# STM32L441CE_2L.net
KiCad netlist of a schematic drawn in EAGLE
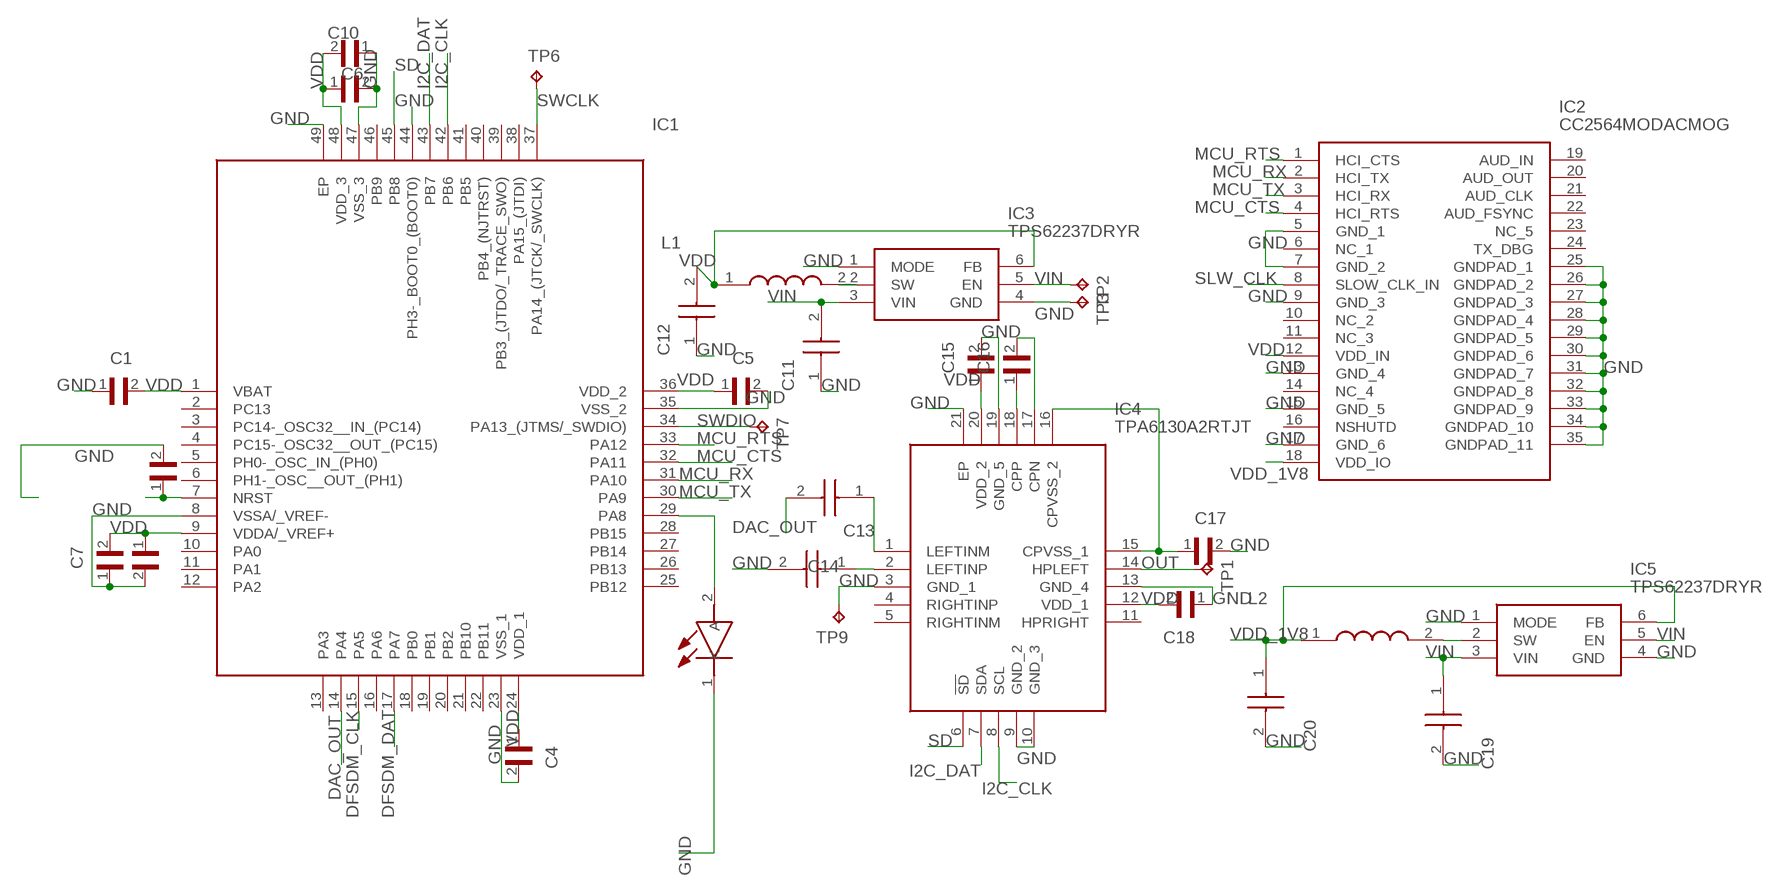
[diagram p0: schematic, sheet 1]
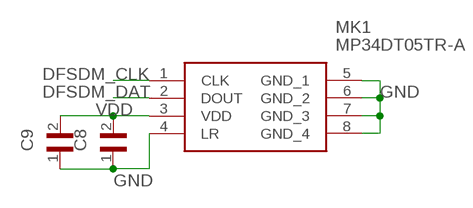
[diagram p1: schematic, sheet 2]

(export (version "E")
  (design (tool "Eeschema 10.0.6"))
  (components
    (comp (ref "C1")
      (value "GRM033C80J104KE15D")
      (footprint "eagle-import:CAPC0603X33N")
      (fields (field (name "DIGI-KEY_PART_NUMBER") "490-10390-1-ND") (field (name "MF") "Murata Electronics"))
      (libsource (lib "eagle-import") (part "GRM033C80J104KE15D"))
    )
    (comp (ref "C2")
      (value "GRM033C80J104KE15D")
      (footprint "eagle-import:CAPC0603X33N")
      (fields (field (name "DIGI-KEY_PART_NUMBER") "490-10390-1-ND") (field (name "MF") "Murata Electronics"))
      (libsource (lib "eagle-import") (part "GRM033C80J104KE15D"))
    )
    (comp (ref "C3")
      (value "GRM033C80J104KE15D")
      (footprint "eagle-import:CAPC0603X33N")
      (fields (field (name "DIGI-KEY_PART_NUMBER") "490-10390-1-ND") (field (name "MF") "Murata Electronics"))
      (libsource (lib "eagle-import") (part "GRM033C80J104KE15D"))
    )
    (comp (ref "C4")
      (value "GRM033C80J104KE15D")
      (footprint "eagle-import:CAPC0603X33N")
      (fields (field (name "DIGI-KEY_PART_NUMBER") "490-10390-1-ND") (field (name "MF") "Murata Electronics"))
      (libsource (lib "eagle-import") (part "GRM033C80J104KE15D"))
    )
    (comp (ref "C5")
      (value "GRM033C80J104KE15D")
      (footprint "eagle-import:CAPC0603X33N")
      (fields (field (name "DIGI-KEY_PART_NUMBER") "490-10390-1-ND") (field (name "MF") "Murata Electronics"))
      (libsource (lib "eagle-import") (part "GRM033C80J104KE15D"))
    )
    (comp (ref "C6")
      (value "GRM033C80J104KE15D")
      (footprint "eagle-import:CAPC0603X33N")
      (fields (field (name "DIGI-KEY_PART_NUMBER") "490-10390-1-ND") (field (name "MF") "Murata Electronics"))
      (libsource (lib "eagle-import") (part "GRM033C80J104KE15D"))
    )
    (comp (ref "C7")
      (value "JMK105C6105KV-F")
      (footprint "eagle-import:CAPC1005X55N")
      (fields (field (name "DIGI-KEY_PART_NUMBER") "587-3381-1-ND") (field (name "MF") "Taiyo Yuden"))
      (libsource (lib "eagle-import") (part "JMK105C6105KV-F"))
    )
    (comp (ref "C10")
      (value "GRM155R60J475ME47D")
      (footprint "eagle-import:CAPC1005X60N")
      (fields (field (name "DIGI-KEY_PART_NUMBER") "490-5915-1-ND") (field (name "MF") "Murata"))
      (libsource (lib "eagle-import") (part "GRM155R60J475ME47D"))
    )
    (comp (ref "C11")
      (value "02016D225MAT2A")
      (footprint "eagle-import:CAPC0603X33N")
      (fields (field (name "MOUSER_PART_NUMBER") "581-02016D225MAT2A"))
      (libsource (lib "eagle-import") (part "02016D225MAT2A"))
    )
    (comp (ref "C12")
      (value "GRM035R60J475ME15D")
      (footprint "eagle-import:CAPC0603X55N")
      (fields (field (name "MOUSER_PART_NUMBER") "81-GRM035R60J475ME5D"))
      (libsource (lib "eagle-import") (part "GRM035R60J475ME15D"))
    )
    (comp (ref "C13")
      (value "CL03A474KQ3NNNC")
      (footprint "eagle-import:CAPC0603X33N")
      (libsource (lib "eagle-import") (part "CL03A474KQ3NNNC"))
    )
    (comp (ref "C14")
      (value "CL03A474KQ3NNNC")
      (footprint "eagle-import:CAPC0603X33N")
      (libsource (lib "eagle-import") (part "CL03A474KQ3NNNC"))
    )
    (comp (ref "C15")
      (value "JMK105C6105KV-F")
      (footprint "eagle-import:CAPC1005X55N")
      (fields (field (name "DIGI-KEY_PART_NUMBER") "587-3381-1-ND") (field (name "MF") "Taiyo Yuden"))
      (libsource (lib "eagle-import") (part "JMK105C6105KV-F"))
    )
    (comp (ref "C16")
      (value "JMK105C6105KV-F")
      (footprint "eagle-import:CAPC1005X55N")
      (fields (field (name "DIGI-KEY_PART_NUMBER") "587-3381-1-ND") (field (name "MF") "Taiyo Yuden"))
      (libsource (lib "eagle-import") (part "JMK105C6105KV-F"))
    )
    (comp (ref "C17")
      (value "JMK105C6105KV-F")
      (footprint "eagle-import:CAPC1005X55N")
      (fields (field (name "DIGI-KEY_PART_NUMBER") "587-3381-1-ND") (field (name "MF") "Taiyo Yuden"))
      (libsource (lib "eagle-import") (part "JMK105C6105KV-F"))
    )
    (comp (ref "C18")
      (value "JMK105C6105KV-F")
      (footprint "eagle-import:CAPC1005X55N")
      (fields (field (name "DIGI-KEY_PART_NUMBER") "587-3381-1-ND") (field (name "MF") "Taiyo Yuden"))
      (libsource (lib "eagle-import") (part "JMK105C6105KV-F"))
    )
    (comp (ref "C19")
      (value "02016D225MAT2A")
      (footprint "eagle-import:CAPC0603X33N")
      (fields (field (name "MOUSER_PART_NUMBER") "581-02016D225MAT2A"))
      (libsource (lib "eagle-import") (part "02016D225MAT2A"))
    )
    (comp (ref "C20")
      (value "GRM035R60J475ME15D")
      (footprint "eagle-import:CAPC0603X55N")
      (fields (field (name "MOUSER_PART_NUMBER") "81-GRM035R60J475ME5D"))
      (libsource (lib "eagle-import") (part "GRM035R60J475ME15D"))
    )
    (comp (ref "IC1")
      (value "STM32L451CEU6")
      (footprint "eagle-import:QFN50P700X700X60-49N")
      (fields (field (name "MOUSER_PART_NUMBER") "511-STM32L451CEU6"))
      (libsource (lib "eagle-import") (part "STM32L451CEU6"))
    )
    (comp (ref "IC2")
      (value "CC2564MODACMOG")
      (footprint "eagle-import:MOG0035A")
      (fields (field (name "MOUSER_PART_NUMBER") "595-CC2564MODACMOG"))
      (libsource (lib "eagle-import") (part "CC2564MODACMOG"))
    )
    (comp (ref "IC3")
      (value "TPS62237DRYR")
      (footprint "eagle-import:SON50P100X145X60-6N")
      (fields (field (name "MOUSER_PART_NUMBER") "595-TPS62237DRYR"))
      (libsource (lib "eagle-import") (part "TPS62237DRYR"))
    )
    (comp (ref "IC4")
      (value "TPA6130A2RTJT")
      (footprint "eagle-import:QFN50P400X400X80-21N")
      (fields (field (name "MOUSER_PART_NUMBER") "595-TPA6130A2RTJT"))
      (libsource (lib "eagle-import") (part "TPA6130A2RTJT"))
    )
    (comp (ref "IC5")
      (value "TPS62237DRYR")
      (footprint "eagle-import:SON50P100X145X60-6N")
      (fields (field (name "MOUSER_PART_NUMBER") "595-TPS62237DRYR"))
      (libsource (lib "eagle-import") (part "TPS62237DRYR"))
    )
    (comp (ref "L1")
      (value "MLZ1005M2R2WT000")
      (footprint "eagle-import:INDC1005X55N")
      (fields (field (name "MOUSER_PART_NUMBER") "810-MLZ1005M2R2WT000"))
      (libsource (lib "eagle-import") (part "MLZ1005M2R2WT000"))
    )
    (comp (ref "L2")
      (value "MLZ1005M2R2WT000")
      (footprint "eagle-import:INDC1005X55N")
      (fields (field (name "MOUSER_PART_NUMBER") "810-MLZ1005M2R2WT000"))
      (libsource (lib "eagle-import") (part "MLZ1005M2R2WT000"))
    )
    (comp (ref "LED1")
      (value "VLMS1500-GS08")
      (footprint "eagle-import:VLMG1500GS08")
      (fields (field (name "MOUSER_PART_NUMBER") "78-VLMS1500-GS08"))
      (libsource (lib "eagle-import") (part "VLMS1500-GS08"))
    )
    (comp (ref "TP1")
      (value "TPTP11R")
      (footprint "eagle-import:TP11R")
      (libsource (lib "eagle-import") (part "TPTP11R"))
    )
    (comp (ref "TP2")
      (value "TPTP11R")
      (footprint "eagle-import:TP11R")
      (libsource (lib "eagle-import") (part "TPTP11R"))
    )
    (comp (ref "TP3")
      (value "TPTP11R")
      (footprint "eagle-import:TP11R")
      (libsource (lib "eagle-import") (part "TPTP11R"))
    )
    (comp (ref "TP6")
      (value "TPTP11R")
      (footprint "eagle-import:TP11R")
      (libsource (lib "eagle-import") (part "TPTP11R"))
    )
    (comp (ref "TP7")
      (value "TPTP11R")
      (footprint "eagle-import:TP11R")
      (libsource (lib "eagle-import") (part "TPTP11R"))
    )
    (comp (ref "TP9")
      (value "TPTP11R")
      (footprint "eagle-import:TP11R")
      (libsource (lib "eagle-import") (part "TPTP11R"))
    )
    (comp (ref "C8")
      (value "JMK105C6105KV-F")
      (footprint "eagle-import:CAPC1005X55N")
      (fields (field (name "DIGI-KEY_PART_NUMBER") "587-3381-1-ND") (field (name "MF") "Taiyo Yuden"))
      (libsource (lib "eagle-import") (part "JMK105C6105KV-F"))
    )
    (comp (ref "C9")
      (value "GRM033C80J104KE15D")
      (footprint "eagle-import:CAPC0603X33N")
      (fields (field (name "DIGI-KEY_PART_NUMBER") "490-10390-1-ND") (field (name "MF") "Murata Electronics"))
      (libsource (lib "eagle-import") (part "GRM033C80J104KE15D"))
    )
    (comp (ref "MK1")
      (value "MP34DT05TR-A")
      (footprint "eagle-import:MP34DT05TRA")
      (fields (field (name "MOUSER_PART_NUMBER") "511-MP34DT05TR-A"))
      (libsource (lib "eagle-import") (part "MP34DT05TR-A"))
    )
  )
  (nets
    (net (code "1") (name "DAC_OUT") (class "Default")
      (node (ref "C13") (pin "2") (pinfunction "2_2") (pintype "bidirectional"))
      (node (ref "IC1") (pin "14") (pinfunction "PA4_14") (pintype "bidirectional"))
    )
    (net (code "2") (name "DFSDM_CLK") (class "Default")
      (node (ref "IC1") (pin "15") (pinfunction "PA5_15") (pintype "bidirectional"))
      (node (ref "MK1") (pin "1") (pinfunction "CLK_1") (pintype "bidirectional"))
    )
    (net (code "3") (name "DFSDM_DAT") (class "Default")
      (node (ref "IC1") (pin "17") (pinfunction "PA7_17") (pintype "bidirectional"))
      (node (ref "MK1") (pin "2") (pinfunction "DOUT_2") (pintype "bidirectional"))
    )
    (net (code "4") (name "GND") (class "Default")
      (node (ref "C1") (pin "1") (pinfunction "1_1") (pintype "passive"))
      (node (ref "C10") (pin "1") (pinfunction "1_1") (pintype "passive"))
      (node (ref "C11") (pin "1") (pinfunction "1_1") (pintype "bidirectional"))
      (node (ref "C12") (pin "1") (pinfunction "1_1") (pintype "bidirectional"))
      (node (ref "C14") (pin "2") (pinfunction "2_2") (pintype "bidirectional"))
      (node (ref "C15") (pin "2") (pinfunction "2_2") (pintype "passive"))
      (node (ref "C17") (pin "2") (pinfunction "2_2") (pintype "passive"))
      (node (ref "C18") (pin "1") (pinfunction "1_1") (pintype "passive"))
      (node (ref "C19") (pin "2") (pinfunction "2_2") (pintype "bidirectional"))
      (node (ref "C2") (pin "2") (pinfunction "2_2") (pintype "passive"))
      (node (ref "C20") (pin "2") (pinfunction "2_2") (pintype "bidirectional"))
      (node (ref "C3") (pin "2") (pinfunction "2_2") (pintype "passive"))
      (node (ref "C4") (pin "2") (pinfunction "2_2") (pintype "passive"))
      (node (ref "C5") (pin "2") (pinfunction "2_2") (pintype "passive"))
      (node (ref "C6") (pin "2") (pinfunction "2_2") (pintype "passive"))
      (node (ref "C7") (pin "1") (pinfunction "1_1") (pintype "passive"))
      (node (ref "C8") (pin "1") (pinfunction "1_1") (pintype "passive"))
      (node (ref "C9") (pin "1") (pinfunction "1_1") (pintype "passive"))
      (node (ref "IC1") (pin "23") (pinfunction "VSS_1_23") (pintype "bidirectional"))
      (node (ref "IC1") (pin "35") (pinfunction "VSS_2_35") (pintype "bidirectional"))
      (node (ref "IC1") (pin "44") (pinfunction "PH3-_BOOT0_(BOOT0)_44") (pintype "bidirectional"))
      (node (ref "IC1") (pin "47") (pinfunction "VSS_3_47") (pintype "bidirectional"))
      (node (ref "IC1") (pin "49") (pinfunction "EP_49") (pintype "bidirectional"))
      (node (ref "IC1") (pin "8") (pinfunction "VSSA/_VREF-_8") (pintype "bidirectional"))
      (node (ref "IC2") (pin "13") (pinfunction "GND_4_13") (pintype "power_in"))
      (node (ref "IC2") (pin "15") (pinfunction "GND_5_15") (pintype "power_in"))
      (node (ref "IC2") (pin "17") (pinfunction "GND_6_17") (pintype "power_in"))
      (node (ref "IC2") (pin "25") (pinfunction "GNDPAD_1_25") (pintype "power_in"))
      (node (ref "IC2") (pin "26") (pinfunction "GNDPAD_2_26") (pintype "power_in"))
      (node (ref "IC2") (pin "27") (pinfunction "GNDPAD_3_27") (pintype "power_in"))
      (node (ref "IC2") (pin "28") (pinfunction "GNDPAD_4_28") (pintype "power_in"))
      (node (ref "IC2") (pin "29") (pinfunction "GNDPAD_5_29") (pintype "power_in"))
      (node (ref "IC2") (pin "30") (pinfunction "GNDPAD_6_30") (pintype "power_in"))
      (node (ref "IC2") (pin "31") (pinfunction "GNDPAD_7_31") (pintype "power_in"))
      (node (ref "IC2") (pin "32") (pinfunction "GNDPAD_8_32") (pintype "power_in"))
      (node (ref "IC2") (pin "33") (pinfunction "GNDPAD_9_33") (pintype "power_in"))
      (node (ref "IC2") (pin "34") (pinfunction "GNDPAD_10_34") (pintype "power_in"))
      (node (ref "IC2") (pin "35") (pinfunction "GNDPAD_11_35") (pintype "power_in"))
      (node (ref "IC2") (pin "5") (pinfunction "GND_1_5") (pintype "power_in"))
      (node (ref "IC2") (pin "7") (pinfunction "GND_2_7") (pintype "power_in"))
      (node (ref "IC2") (pin "9") (pinfunction "GND_3_9") (pintype "power_in"))
      (node (ref "IC3") (pin "1") (pinfunction "MODE_1") (pintype "bidirectional"))
      (node (ref "IC3") (pin "4") (pinfunction "GND_4") (pintype "bidirectional"))
      (node (ref "IC4") (pin "10") (pinfunction "GND_3_10") (pintype "bidirectional"))
      (node (ref "IC4") (pin "13") (pinfunction "GND_4_13") (pintype "bidirectional"))
      (node (ref "IC4") (pin "19") (pinfunction "GND_5_19") (pintype "bidirectional"))
      (node (ref "IC4") (pin "21") (pinfunction "EP_21") (pintype "bidirectional"))
      (node (ref "IC4") (pin "3") (pinfunction "GND_1_3") (pintype "bidirectional"))
      (node (ref "IC4") (pin "9") (pinfunction "GND_2_9") (pintype "bidirectional"))
      (node (ref "IC5") (pin "1") (pinfunction "MODE_1") (pintype "bidirectional"))
      (node (ref "IC5") (pin "4") (pinfunction "GND_4") (pintype "bidirectional"))
      (node (ref "LED1") (pin "1") (pinfunction "K_1") (pintype "bidirectional"))
      (node (ref "MK1") (pin "4") (pinfunction "LR_4") (pintype "bidirectional"))
      (node (ref "MK1") (pin "5") (pinfunction "GND_1_5") (pintype "bidirectional"))
      (node (ref "MK1") (pin "6") (pinfunction "GND_2_6") (pintype "bidirectional"))
      (node (ref "MK1") (pin "7") (pinfunction "GND_3_7") (pintype "bidirectional"))
      (node (ref "MK1") (pin "8") (pinfunction "GND_4_8") (pintype "bidirectional"))
      (node (ref "TP3") (pin "TP") (pinfunction "TP_TP") (pintype "input"))
      (node (ref "TP9") (pin "TP") (pinfunction "TP_TP") (pintype "input"))
    )
    (net (code "5") (name "I2C_CLK") (class "Default")
      (node (ref "IC1") (pin "42") (pinfunction "PB6_42") (pintype "bidirectional"))
      (node (ref "IC4") (pin "8") (pinfunction "SCL_8") (pintype "bidirectional"))
    )
    (net (code "6") (name "I2C_DAT") (class "Default")
      (node (ref "IC1") (pin "43") (pinfunction "PB7_43") (pintype "bidirectional"))
      (node (ref "IC4") (pin "7") (pinfunction "SDA_7") (pintype "bidirectional"))
    )
    (net (code "7") (name "MCU_CTS") (class "Default")
      (node (ref "IC1") (pin "32") (pinfunction "PA11_32") (pintype "bidirectional"))
      (node (ref "IC2") (pin "4") (pinfunction "HCI_RTS_4") (pintype "output"))
    )
    (net (code "8") (name "MCU_RTS") (class "Default")
      (node (ref "IC1") (pin "33") (pinfunction "PA12_33") (pintype "bidirectional"))
      (node (ref "IC2") (pin "1") (pinfunction "HCI_CTS_1") (pintype "input"))
    )
    (net (code "9") (name "MCU_RX") (class "Default")
      (node (ref "IC1") (pin "31") (pinfunction "PA10_31") (pintype "bidirectional"))
      (node (ref "IC2") (pin "2") (pinfunction "HCI_TX_2") (pintype "output"))
    )
    (net (code "10") (name "MCU_TX") (class "Default")
      (node (ref "IC1") (pin "30") (pinfunction "PA9_30") (pintype "bidirectional"))
      (node (ref "IC2") (pin "3") (pinfunction "HCI_RX_3") (pintype "input"))
    )
    (net (code "11") (name "Net-(IC1-NRST)") (class "Default")
      (node (ref "C2") (pin "1") (pinfunction "1_1") (pintype "passive"))
      (node (ref "IC1") (pin "7") (pinfunction "NRST_7") (pintype "bidirectional"))
    )
    (net (code "12") (name "Net-(IC1-PA8)") (class "Default")
      (node (ref "IC1") (pin "29") (pinfunction "PA8_29") (pintype "bidirectional"))
      (node (ref "LED1") (pin "2") (pinfunction "A_2") (pintype "bidirectional"))
    )
    (net (code "13") (name "Net-(IC3-SW)") (class "Default")
      (node (ref "IC3") (pin "2") (pinfunction "SW_2") (pintype "bidirectional"))
      (node (ref "L1") (pin "2") (pinfunction "2_2") (pintype "bidirectional"))
    )
    (net (code "14") (name "Net-(IC4-CPN)") (class "Default")
      (node (ref "C16") (pin "2") (pinfunction "2_2") (pintype "passive"))
      (node (ref "IC4") (pin "17") (pinfunction "CPN_17") (pintype "bidirectional"))
    )
    (net (code "15") (name "Net-(IC4-CPP)") (class "Default")
      (node (ref "C16") (pin "1") (pinfunction "1_1") (pintype "passive"))
      (node (ref "IC4") (pin "18") (pinfunction "CPP_18") (pintype "bidirectional"))
    )
    (net (code "16") (name "Net-(IC4-CPVSS_1)") (class "Default")
      (node (ref "C17") (pin "1") (pinfunction "1_1") (pintype "passive"))
      (node (ref "IC4") (pin "15") (pinfunction "CPVSS_1_15") (pintype "bidirectional"))
      (node (ref "IC4") (pin "16") (pinfunction "CPVSS_2_16") (pintype "bidirectional"))
    )
    (net (code "17") (name "Net-(IC4-LEFTINM)") (class "Default")
      (node (ref "C13") (pin "1") (pinfunction "1_1") (pintype "bidirectional"))
      (node (ref "IC4") (pin "1") (pinfunction "LEFTINM_1") (pintype "bidirectional"))
    )
    (net (code "18") (name "Net-(IC4-LEFTINP)") (class "Default")
      (node (ref "C14") (pin "1") (pinfunction "1_1") (pintype "bidirectional"))
      (node (ref "IC4") (pin "2") (pinfunction "LEFTINP_2") (pintype "bidirectional"))
    )
    (net (code "19") (name "Net-(IC5-SW)") (class "Default")
      (node (ref "IC5") (pin "2") (pinfunction "SW_2") (pintype "bidirectional"))
      (node (ref "L2") (pin "2") (pinfunction "2_2") (pintype "bidirectional"))
    )
    (net (code "20") (name "OUT") (class "Default")
      (node (ref "IC4") (pin "14") (pinfunction "HPLEFT_14") (pintype "bidirectional"))
      (node (ref "TP1") (pin "TP") (pinfunction "TP_TP") (pintype "input"))
    )
    (net (code "21") (name "SD") (class "Default")
      (node (ref "IC1") (pin "45") (pinfunction "PB8_45") (pintype "bidirectional"))
      (node (ref "IC4") (pin "6") (pinfunction "~{SD}_6") (pintype "bidirectional"))
    )
    (net (code "22") (name "SLW_CLK") (class "Default")
      (node (ref "IC2") (pin "8") (pinfunction "SLOW_CLK_IN_8") (pintype "input"))
    )
    (net (code "23") (name "SWCLK") (class "Default")
      (node (ref "IC1") (pin "37") (pinfunction "PA14_(JTCK/_SWCLK)_37") (pintype "bidirectional"))
      (node (ref "TP6") (pin "TP") (pinfunction "TP_TP") (pintype "input"))
    )
    (net (code "24") (name "SWDIO") (class "Default")
      (node (ref "IC1") (pin "34") (pinfunction "PA13_(JTMS/_SWDIO)_34") (pintype "bidirectional"))
      (node (ref "TP7") (pin "TP") (pinfunction "TP_TP") (pintype "input"))
    )
    (net (code "25") (name "VDD") (class "Default")
      (node (ref "C1") (pin "2") (pinfunction "2_2") (pintype "passive"))
      (node (ref "C10") (pin "2") (pinfunction "2_2") (pintype "passive"))
      (node (ref "C12") (pin "2") (pinfunction "2_2") (pintype "bidirectional"))
      (node (ref "C15") (pin "1") (pinfunction "1_1") (pintype "passive"))
      (node (ref "C18") (pin "2") (pinfunction "2_2") (pintype "passive"))
      (node (ref "C3") (pin "1") (pinfunction "1_1") (pintype "passive"))
      (node (ref "C4") (pin "1") (pinfunction "1_1") (pintype "passive"))
      (node (ref "C5") (pin "1") (pinfunction "1_1") (pintype "passive"))
      (node (ref "C6") (pin "1") (pinfunction "1_1") (pintype "passive"))
      (node (ref "C7") (pin "2") (pinfunction "2_2") (pintype "passive"))
      (node (ref "C8") (pin "2") (pinfunction "2_2") (pintype "passive"))
      (node (ref "C9") (pin "2") (pinfunction "2_2") (pintype "passive"))
      (node (ref "IC1") (pin "1") (pinfunction "VBAT_1") (pintype "bidirectional"))
      (node (ref "IC1") (pin "24") (pinfunction "VDD_1_24") (pintype "bidirectional"))
      (node (ref "IC1") (pin "36") (pinfunction "VDD_2_36") (pintype "bidirectional"))
      (node (ref "IC1") (pin "48") (pinfunction "VDD_3_48") (pintype "bidirectional"))
      (node (ref "IC1") (pin "9") (pinfunction "VDDA/_VREF+_9") (pintype "bidirectional"))
      (node (ref "IC2") (pin "12") (pinfunction "VDD_IN_12") (pintype "input"))
      (node (ref "IC3") (pin "6") (pinfunction "FB_6") (pintype "bidirectional"))
      (node (ref "IC4") (pin "12") (pinfunction "VDD_1_12") (pintype "bidirectional"))
      (node (ref "IC4") (pin "20") (pinfunction "VDD_2_20") (pintype "bidirectional"))
      (node (ref "L1") (pin "1") (pinfunction "1_1") (pintype "bidirectional"))
      (node (ref "MK1") (pin "3") (pinfunction "VDD_3") (pintype "bidirectional"))
    )
    (net (code "26") (name "VDD_1V8") (class "Default")
      (node (ref "C20") (pin "1") (pinfunction "1_1") (pintype "bidirectional"))
      (node (ref "IC2") (pin "18") (pinfunction "VDD_IO_18") (pintype "bidirectional"))
      (node (ref "IC5") (pin "6") (pinfunction "FB_6") (pintype "bidirectional"))
      (node (ref "L2") (pin "1") (pinfunction "1_1") (pintype "bidirectional"))
    )
    (net (code "27") (name "VIN") (class "Default")
      (node (ref "C11") (pin "2") (pinfunction "2_2") (pintype "bidirectional"))
      (node (ref "C19") (pin "1") (pinfunction "1_1") (pintype "bidirectional"))
      (node (ref "IC3") (pin "3") (pinfunction "VIN_3") (pintype "bidirectional"))
      (node (ref "IC3") (pin "5") (pinfunction "EN_5") (pintype "bidirectional"))
      (node (ref "IC5") (pin "3") (pinfunction "VIN_3") (pintype "bidirectional"))
      (node (ref "IC5") (pin "5") (pinfunction "EN_5") (pintype "bidirectional"))
      (node (ref "TP2") (pin "TP") (pinfunction "TP_TP") (pintype "input"))
    )
    (net (code "28") (name "unconnected-(IC1-PA0-Pad10)") (class "Default")
      (node (ref "IC1") (pin "10") (pinfunction "PA0_10") (pintype "bidirectional"))
    )
    (net (code "29") (name "unconnected-(IC1-PA1-Pad11)") (class "Default")
      (node (ref "IC1") (pin "11") (pinfunction "PA1_11") (pintype "bidirectional"))
    )
    (net (code "30") (name "unconnected-(IC1-PA2-Pad12)") (class "Default")
      (node (ref "IC1") (pin "12") (pinfunction "PA2_12") (pintype "bidirectional"))
    )
    (net (code "31") (name "unconnected-(IC1-PA3-Pad13)") (class "Default")
      (node (ref "IC1") (pin "13") (pinfunction "PA3_13") (pintype "bidirectional"))
    )
    (net (code "32") (name "unconnected-(IC1-PA6-Pad16)") (class "Default")
      (node (ref "IC1") (pin "16") (pinfunction "PA6_16") (pintype "bidirectional"))
    )
    (net (code "33") (name "unconnected-(IC1-PA15_(JTDI)-Pad38)") (class "Default")
      (node (ref "IC1") (pin "38") (pinfunction "PA15_(JTDI)_38") (pintype "bidirectional"))
    )
    (net (code "34") (name "unconnected-(IC1-PB0-Pad18)") (class "Default")
      (node (ref "IC1") (pin "18") (pinfunction "PB0_18") (pintype "bidirectional"))
    )
    (net (code "35") (name "unconnected-(IC1-PB1-Pad19)") (class "Default")
      (node (ref "IC1") (pin "19") (pinfunction "PB1_19") (pintype "bidirectional"))
    )
    (net (code "36") (name "unconnected-(IC1-PB2-Pad20)") (class "Default")
      (node (ref "IC1") (pin "20") (pinfunction "PB2_20") (pintype "bidirectional"))
    )
    (net (code "37") (name "unconnected-(IC1-PB3_(JTDO{slash}_TRACE_SWO)-Pad39)") (class "Default")
      (node (ref "IC1") (pin "39") (pinfunction "PB3_(JTDO/_TRACE_SWO)_39") (pintype "bidirectional"))
    )
    (net (code "38") (name "unconnected-(IC1-PB4_(NJTRST)-Pad40)") (class "Default")
      (node (ref "IC1") (pin "40") (pinfunction "PB4_(NJTRST)_40") (pintype "bidirectional"))
    )
    (net (code "39") (name "unconnected-(IC1-PB5-Pad41)") (class "Default")
      (node (ref "IC1") (pin "41") (pinfunction "PB5_41") (pintype "bidirectional"))
    )
    (net (code "40") (name "unconnected-(IC1-PB9-Pad46)") (class "Default")
      (node (ref "IC1") (pin "46") (pinfunction "PB9_46") (pintype "bidirectional"))
    )
    (net (code "41") (name "unconnected-(IC1-PB10-Pad21)") (class "Default")
      (node (ref "IC1") (pin "21") (pinfunction "PB10_21") (pintype "bidirectional"))
    )
    (net (code "42") (name "unconnected-(IC1-PB11-Pad22)") (class "Default")
      (node (ref "IC1") (pin "22") (pinfunction "PB11_22") (pintype "bidirectional"))
    )
    (net (code "43") (name "unconnected-(IC1-PB12-Pad25)") (class "Default")
      (node (ref "IC1") (pin "25") (pinfunction "PB12_25") (pintype "bidirectional"))
    )
    (net (code "44") (name "unconnected-(IC1-PB13-Pad26)") (class "Default")
      (node (ref "IC1") (pin "26") (pinfunction "PB13_26") (pintype "bidirectional"))
    )
    (net (code "45") (name "unconnected-(IC1-PB14-Pad27)") (class "Default")
      (node (ref "IC1") (pin "27") (pinfunction "PB14_27") (pintype "bidirectional"))
    )
    (net (code "46") (name "unconnected-(IC1-PB15-Pad28)") (class "Default")
      (node (ref "IC1") (pin "28") (pinfunction "PB15_28") (pintype "bidirectional"))
    )
    (net (code "47") (name "unconnected-(IC1-PC13-Pad2)") (class "Default")
      (node (ref "IC1") (pin "2") (pinfunction "PC13_2") (pintype "bidirectional"))
    )
    (net (code "48") (name "unconnected-(IC1-PC14-_OSC32__IN_(PC14)-Pad3)") (class "Default")
      (node (ref "IC1") (pin "3") (pinfunction "PC14-_OSC32__IN_(PC14)_3") (pintype "bidirectional"))
    )
    (net (code "49") (name "unconnected-(IC1-PC15-_OSC32__OUT_(PC15)-Pad4)") (class "Default")
      (node (ref "IC1") (pin "4") (pinfunction "PC15-_OSC32__OUT_(PC15)_4") (pintype "bidirectional"))
    )
    (net (code "50") (name "unconnected-(IC1-PH0-_OSC_IN_(PH0)-Pad5)") (class "Default")
      (node (ref "IC1") (pin "5") (pinfunction "PH0-_OSC_IN_(PH0)_5") (pintype "bidirectional"))
    )
    (net (code "51") (name "unconnected-(IC1-PH1-_OSC__OUT_(PH1)-Pad6)") (class "Default")
      (node (ref "IC1") (pin "6") (pinfunction "PH1-_OSC__OUT_(PH1)_6") (pintype "bidirectional"))
    )
    (net (code "52") (name "unconnected-(IC2-AUD_CLK-Pad21)") (class "Default")
      (node (ref "IC2") (pin "21") (pinfunction "AUD_CLK_21") (pintype "bidirectional"))
    )
    (net (code "53") (name "unconnected-(IC2-AUD_FSYNC-Pad22)") (class "Default")
      (node (ref "IC2") (pin "22") (pinfunction "AUD_FSYNC_22") (pintype "bidirectional"))
    )
    (net (code "54") (name "unconnected-(IC2-AUD_IN-Pad19)") (class "Default")
      (node (ref "IC2") (pin "19") (pinfunction "AUD_IN_19") (pintype "bidirectional"))
    )
    (net (code "55") (name "unconnected-(IC2-AUD_OUT-Pad20)") (class "Default")
      (node (ref "IC2") (pin "20") (pinfunction "AUD_OUT_20") (pintype "bidirectional"))
    )
    (net (code "56") (name "unconnected-(IC2-NC_1-Pad6)") (class "Default")
      (node (ref "IC2") (pin "6") (pinfunction "NC_1_6") (pintype "bidirectional"))
    )
    (net (code "57") (name "unconnected-(IC2-NC_2-Pad10)") (class "Default")
      (node (ref "IC2") (pin "10") (pinfunction "NC_2_10") (pintype "bidirectional"))
    )
    (net (code "58") (name "unconnected-(IC2-NC_3-Pad11)") (class "Default")
      (node (ref "IC2") (pin "11") (pinfunction "NC_3_11") (pintype "bidirectional"))
    )
    (net (code "59") (name "unconnected-(IC2-NC_4-Pad14)") (class "Default")
      (node (ref "IC2") (pin "14") (pinfunction "NC_4_14") (pintype "bidirectional"))
    )
    (net (code "60") (name "unconnected-(IC2-NC_5-Pad23)") (class "Default")
      (node (ref "IC2") (pin "23") (pinfunction "NC_5_23") (pintype "bidirectional"))
    )
    (net (code "61") (name "unconnected-(IC2-NSHUTD-Pad16)") (class "Default")
      (node (ref "IC2") (pin "16") (pinfunction "NSHUTD_16") (pintype "input"))
    )
    (net (code "62") (name "unconnected-(IC2-TX_DBG-Pad24)") (class "Default")
      (node (ref "IC2") (pin "24") (pinfunction "TX_DBG_24") (pintype "output"))
    )
    (net (code "63") (name "unconnected-(IC4-HPRIGHT-Pad11)") (class "Default")
      (node (ref "IC4") (pin "11") (pinfunction "HPRIGHT_11") (pintype "bidirectional"))
    )
    (net (code "64") (name "unconnected-(IC4-RIGHTINM-Pad5)") (class "Default")
      (node (ref "IC4") (pin "5") (pinfunction "RIGHTINM_5") (pintype "bidirectional"))
    )
    (net (code "65") (name "unconnected-(IC4-RIGHTINP-Pad4)") (class "Default")
      (node (ref "IC4") (pin "4") (pinfunction "RIGHTINP_4") (pintype "bidirectional"))
    )
  )
)
